# RPi_motor_driver.net
KiCad netlist of a schematic drawn in EAGLE
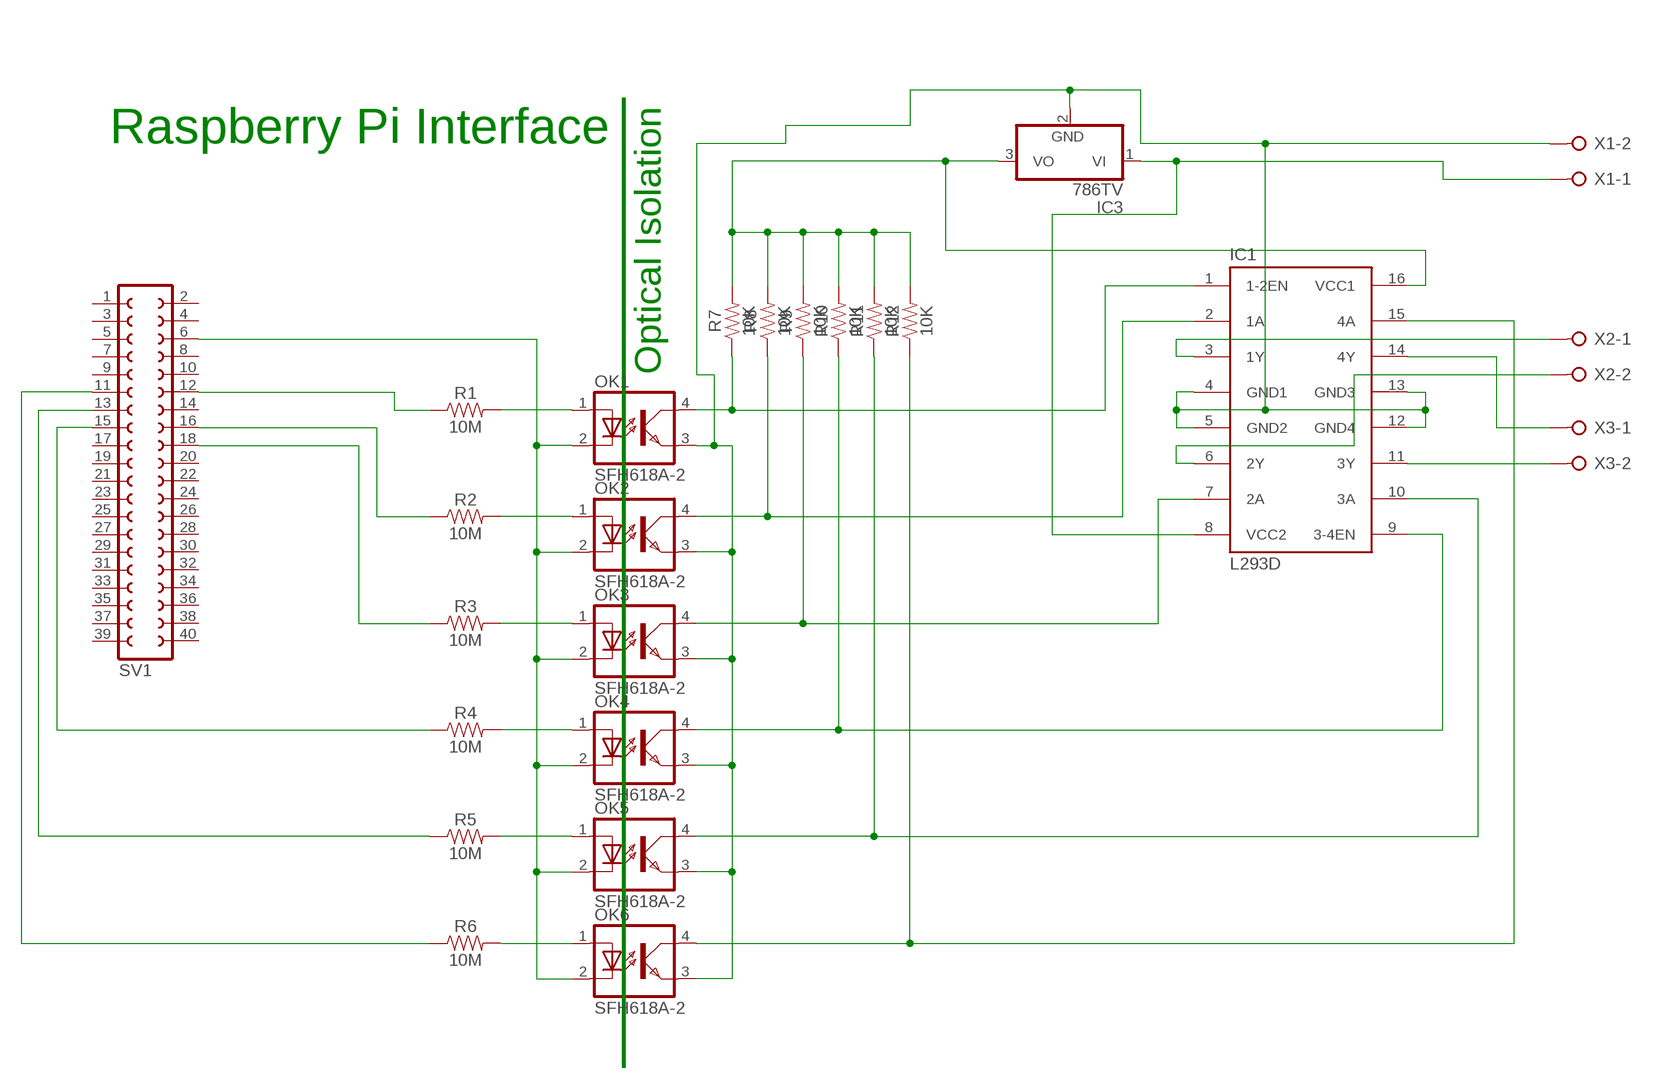
[diagram p0: schematic, sheet 1]

(export (version "E")
  (design (tool "Eeschema 10.0.6"))
  (components
    (comp (ref "IC1")
      (value "L293D")
      (footprint "eagle-import:DIL16")
      (libsource (lib "eagle-import") (part "L293D"))
    )
    (comp (ref "IC3")
      (value "786TV")
      (footprint "eagle-import:TO220V")
      (libsource (lib "eagle-import") (part "78TV6"))
    )
    (comp (ref "OK1")
      (value "SFH618A-2")
      (footprint "eagle-import:DIP4")
      (fields (field (name "MF") "VISHAY/TELEFUNKEN"))
      (libsource (lib "eagle-import") (part "SFH618?A-2"))
    )
    (comp (ref "OK2")
      (value "SFH618A-2")
      (footprint "eagle-import:DIP4")
      (fields (field (name "MF") "VISHAY/TELEFUNKEN"))
      (libsource (lib "eagle-import") (part "SFH618?A-2"))
    )
    (comp (ref "OK3")
      (value "SFH618A-2")
      (footprint "eagle-import:DIP4")
      (fields (field (name "MF") "VISHAY/TELEFUNKEN"))
      (libsource (lib "eagle-import") (part "SFH618?A-2"))
    )
    (comp (ref "OK4")
      (value "SFH618A-2")
      (footprint "eagle-import:DIP4")
      (fields (field (name "MF") "VISHAY/TELEFUNKEN"))
      (libsource (lib "eagle-import") (part "SFH618?A-2"))
    )
    (comp (ref "OK5")
      (value "SFH618A-2")
      (footprint "eagle-import:DIP4")
      (fields (field (name "MF") "VISHAY/TELEFUNKEN"))
      (libsource (lib "eagle-import") (part "SFH618?A-2"))
    )
    (comp (ref "OK6")
      (value "SFH618A-2")
      (footprint "eagle-import:DIP4")
      (fields (field (name "MF") "VISHAY/TELEFUNKEN"))
      (libsource (lib "eagle-import") (part "SFH618?A-2"))
    )
    (comp (ref "R1")
      (value "10M")
      (footprint "eagle-import:AXIAL-0.3")
      (libsource (lib "eagle-import") (part "10MOHM-HORIZ-1/4W-5%"))
    )
    (comp (ref "R2")
      (value "10M")
      (footprint "eagle-import:AXIAL-0.3")
      (libsource (lib "eagle-import") (part "10MOHM-HORIZ-1/4W-5%"))
    )
    (comp (ref "R3")
      (value "10M")
      (footprint "eagle-import:AXIAL-0.3")
      (libsource (lib "eagle-import") (part "10MOHM-HORIZ-1/4W-5%"))
    )
    (comp (ref "R4")
      (value "10M")
      (footprint "eagle-import:AXIAL-0.3")
      (libsource (lib "eagle-import") (part "10MOHM-HORIZ-1/4W-5%"))
    )
    (comp (ref "R5")
      (value "10M")
      (footprint "eagle-import:AXIAL-0.3")
      (libsource (lib "eagle-import") (part "10MOHM-HORIZ-1/4W-5%"))
    )
    (comp (ref "R6")
      (value "10M")
      (footprint "eagle-import:AXIAL-0.3")
      (libsource (lib "eagle-import") (part "10MOHM-HORIZ-1/4W-5%"))
    )
    (comp (ref "R7")
      (value "10K")
      (footprint "eagle-import:AXIAL-0.3")
      (libsource (lib "eagle-import") (part "10MOHM-HORIZ-1/4W-5%"))
    )
    (comp (ref "R8")
      (value "10K")
      (footprint "eagle-import:AXIAL-0.3")
      (libsource (lib "eagle-import") (part "10MOHM-HORIZ-1/4W-5%"))
    )
    (comp (ref "R9")
      (value "10K")
      (footprint "eagle-import:AXIAL-0.3")
      (libsource (lib "eagle-import") (part "10MOHM-HORIZ-1/4W-5%"))
    )
    (comp (ref "R10")
      (value "10K")
      (footprint "eagle-import:AXIAL-0.3")
      (libsource (lib "eagle-import") (part "10MOHM-HORIZ-1/4W-5%"))
    )
    (comp (ref "R11")
      (value "10K")
      (footprint "eagle-import:AXIAL-0.3")
      (libsource (lib "eagle-import") (part "10MOHM-HORIZ-1/4W-5%"))
    )
    (comp (ref "R12")
      (value "10K")
      (footprint "eagle-import:AXIAL-0.3")
      (libsource (lib "eagle-import") (part "10MOHM-HORIZ-1/4W-5%"))
    )
    (comp (ref "SV1")
      (value "FE20-2")
      (footprint "eagle-import:FE20-2")
      (libsource (lib "eagle-import") (part "FE20-2"))
    )
    (comp (ref "X1")
      (value "W237-02P")
      (footprint "eagle-import:W237-132")
      (libsource (lib "eagle-import") (part "W237-02P"))
    )
    (comp (ref "X2")
      (value "W237-02P")
      (footprint "eagle-import:W237-132")
      (libsource (lib "eagle-import") (part "W237-02P"))
    )
    (comp (ref "X3")
      (value "W237-02P")
      (footprint "eagle-import:W237-132")
      (libsource (lib "eagle-import") (part "W237-02P"))
    )
  )
  (nets
    (net (code "1") (name "Net-(IC1-1-2EN)") (class "Default")
      (node (ref "IC1") (pin "1") (pinfunction "1-2EN_1") (pintype "input"))
      (node (ref "OK1") (pin "4") (pinfunction "COL_4") (pintype "passive"))
      (node (ref "R7") (pin "P$1") (pinfunction "1_P$1") (pintype "passive"))
    )
    (net (code "2") (name "Net-(IC1-1A)") (class "Default")
      (node (ref "IC1") (pin "2") (pinfunction "1A_2") (pintype "input"))
      (node (ref "OK2") (pin "4") (pinfunction "COL_4") (pintype "passive"))
      (node (ref "R8") (pin "P$1") (pinfunction "1_P$1") (pintype "passive"))
    )
    (net (code "3") (name "Net-(IC1-1Y)") (class "Default")
      (node (ref "IC1") (pin "3") (pinfunction "1Y_3") (pintype "output"))
      (node (ref "X2") (pin "1") (pinfunction "KL_1") (pintype "passive"))
    )
    (net (code "4") (name "Net-(IC1-2A)") (class "Default")
      (node (ref "IC1") (pin "7") (pinfunction "2A_7") (pintype "input"))
      (node (ref "OK3") (pin "4") (pinfunction "COL_4") (pintype "passive"))
      (node (ref "R9") (pin "P$1") (pinfunction "1_P$1") (pintype "passive"))
    )
    (net (code "5") (name "Net-(IC1-2Y)") (class "Default")
      (node (ref "IC1") (pin "6") (pinfunction "2Y_6") (pintype "output"))
      (node (ref "X2") (pin "2") (pinfunction "KL_2") (pintype "passive"))
    )
    (net (code "6") (name "Net-(IC1-3-4EN)") (class "Default")
      (node (ref "IC1") (pin "9") (pinfunction "3-4EN_9") (pintype "input"))
      (node (ref "OK4") (pin "4") (pinfunction "COL_4") (pintype "passive"))
      (node (ref "R10") (pin "P$1") (pinfunction "1_P$1") (pintype "passive"))
    )
    (net (code "7") (name "Net-(IC1-3A)") (class "Default")
      (node (ref "IC1") (pin "10") (pinfunction "3A_10") (pintype "input"))
      (node (ref "OK5") (pin "4") (pinfunction "COL_4") (pintype "passive"))
      (node (ref "R11") (pin "P$1") (pinfunction "1_P$1") (pintype "passive"))
    )
    (net (code "8") (name "Net-(IC1-3Y)") (class "Default")
      (node (ref "IC1") (pin "11") (pinfunction "3Y_11") (pintype "output"))
      (node (ref "X3") (pin "2") (pinfunction "KL_2") (pintype "passive"))
    )
    (net (code "9") (name "Net-(IC1-4A)") (class "Default")
      (node (ref "IC1") (pin "15") (pinfunction "4A_15") (pintype "input"))
      (node (ref "OK6") (pin "4") (pinfunction "COL_4") (pintype "passive"))
      (node (ref "R12") (pin "P$1") (pinfunction "1_P$1") (pintype "passive"))
    )
    (net (code "10") (name "Net-(IC1-4Y)") (class "Default")
      (node (ref "IC1") (pin "14") (pinfunction "4Y_14") (pintype "output"))
      (node (ref "X3") (pin "1") (pinfunction "KL_1") (pintype "passive"))
    )
    (net (code "11") (name "Net-(IC1-GND1)") (class "Default")
      (node (ref "IC1") (pin "12") (pinfunction "GND4_12") (pintype "power_in"))
      (node (ref "IC1") (pin "13") (pinfunction "GND3_13") (pintype "power_in"))
      (node (ref "IC1") (pin "4") (pinfunction "GND1_4") (pintype "power_in"))
      (node (ref "IC1") (pin "5") (pinfunction "GND2_5") (pintype "power_in"))
      (node (ref "IC3") (pin "2") (pinfunction "GND_2") (pintype "passive"))
      (node (ref "OK1") (pin "3") (pinfunction "EMIT_3") (pintype "passive"))
      (node (ref "OK2") (pin "3") (pinfunction "EMIT_3") (pintype "passive"))
      (node (ref "OK3") (pin "3") (pinfunction "EMIT_3") (pintype "passive"))
      (node (ref "OK4") (pin "3") (pinfunction "EMIT_3") (pintype "passive"))
      (node (ref "OK5") (pin "3") (pinfunction "EMIT_3") (pintype "passive"))
      (node (ref "OK6") (pin "3") (pinfunction "EMIT_3") (pintype "passive"))
      (node (ref "X1") (pin "2") (pinfunction "KL_2") (pintype "passive"))
    )
    (net (code "12") (name "Net-(IC1-VCC1)") (class "Default")
      (node (ref "IC1") (pin "16") (pinfunction "VCC1_16") (pintype "power_in"))
      (node (ref "IC3") (pin "3") (pinfunction "VO_3") (pintype "passive"))
      (node (ref "R10") (pin "P$2") (pinfunction "2_P$2") (pintype "passive"))
      (node (ref "R11") (pin "P$2") (pinfunction "2_P$2") (pintype "passive"))
      (node (ref "R12") (pin "P$2") (pinfunction "2_P$2") (pintype "passive"))
      (node (ref "R7") (pin "P$2") (pinfunction "2_P$2") (pintype "passive"))
      (node (ref "R8") (pin "P$2") (pinfunction "2_P$2") (pintype "passive"))
      (node (ref "R9") (pin "P$2") (pinfunction "2_P$2") (pintype "passive"))
    )
    (net (code "13") (name "Net-(IC1-VCC2)") (class "Default")
      (node (ref "IC1") (pin "8") (pinfunction "VCC2_8") (pintype "power_in"))
      (node (ref "IC3") (pin "1") (pinfunction "VI_1") (pintype "input"))
      (node (ref "X1") (pin "1") (pinfunction "KL_1") (pintype "passive"))
    )
    (net (code "14") (name "Net-(OK1-A)") (class "Default")
      (node (ref "OK1") (pin "1") (pinfunction "A_1") (pintype "passive"))
      (node (ref "R1") (pin "P$2") (pinfunction "2_P$2") (pintype "passive"))
    )
    (net (code "15") (name "Net-(OK1-C)") (class "Default")
      (node (ref "OK1") (pin "2") (pinfunction "C_2") (pintype "passive"))
      (node (ref "OK2") (pin "2") (pinfunction "C_2") (pintype "passive"))
      (node (ref "OK3") (pin "2") (pinfunction "C_2") (pintype "passive"))
      (node (ref "OK4") (pin "2") (pinfunction "C_2") (pintype "passive"))
      (node (ref "OK5") (pin "2") (pinfunction "C_2") (pintype "passive"))
      (node (ref "OK6") (pin "2") (pinfunction "C_2") (pintype "passive"))
      (node (ref "SV1") (pin "6") (pinfunction "6_6") (pintype "passive"))
    )
    (net (code "16") (name "Net-(OK2-A)") (class "Default")
      (node (ref "OK2") (pin "1") (pinfunction "A_1") (pintype "passive"))
      (node (ref "R2") (pin "P$2") (pinfunction "2_P$2") (pintype "passive"))
    )
    (net (code "17") (name "Net-(OK3-A)") (class "Default")
      (node (ref "OK3") (pin "1") (pinfunction "A_1") (pintype "passive"))
      (node (ref "R3") (pin "P$2") (pinfunction "2_P$2") (pintype "passive"))
    )
    (net (code "18") (name "Net-(OK4-A)") (class "Default")
      (node (ref "OK4") (pin "1") (pinfunction "A_1") (pintype "passive"))
      (node (ref "R4") (pin "P$2") (pinfunction "2_P$2") (pintype "passive"))
    )
    (net (code "19") (name "Net-(OK5-A)") (class "Default")
      (node (ref "OK5") (pin "1") (pinfunction "A_1") (pintype "passive"))
      (node (ref "R5") (pin "P$2") (pinfunction "2_P$2") (pintype "passive"))
    )
    (net (code "20") (name "Net-(OK6-A)") (class "Default")
      (node (ref "OK6") (pin "1") (pinfunction "A_1") (pintype "passive"))
      (node (ref "R6") (pin "P$2") (pinfunction "2_P$2") (pintype "passive"))
    )
    (net (code "21") (name "Net-(R1-1)") (class "Default")
      (node (ref "R1") (pin "P$1") (pinfunction "1_P$1") (pintype "passive"))
      (node (ref "SV1") (pin "12") (pinfunction "12_12") (pintype "passive"))
    )
    (net (code "22") (name "Net-(R2-1)") (class "Default")
      (node (ref "R2") (pin "P$1") (pinfunction "1_P$1") (pintype "passive"))
      (node (ref "SV1") (pin "16") (pinfunction "16_16") (pintype "passive"))
    )
    (net (code "23") (name "Net-(R3-1)") (class "Default")
      (node (ref "R3") (pin "P$1") (pinfunction "1_P$1") (pintype "passive"))
      (node (ref "SV1") (pin "18") (pinfunction "18_18") (pintype "passive"))
    )
    (net (code "24") (name "Net-(R4-1)") (class "Default")
      (node (ref "R4") (pin "P$1") (pinfunction "1_P$1") (pintype "passive"))
      (node (ref "SV1") (pin "15") (pinfunction "15_15") (pintype "passive"))
    )
    (net (code "25") (name "Net-(R5-1)") (class "Default")
      (node (ref "R5") (pin "P$1") (pinfunction "1_P$1") (pintype "passive"))
      (node (ref "SV1") (pin "13") (pinfunction "13_13") (pintype "passive"))
    )
    (net (code "26") (name "Net-(R6-1)") (class "Default")
      (node (ref "R6") (pin "P$1") (pinfunction "1_P$1") (pintype "passive"))
      (node (ref "SV1") (pin "11") (pinfunction "11_11") (pintype "passive"))
    )
    (net (code "27") (name "unconnected-(SV1-Pad1)") (class "Default")
      (node (ref "SV1") (pin "1") (pinfunction "1_1") (pintype "passive"))
    )
    (net (code "28") (name "unconnected-(SV1-Pad2)") (class "Default")
      (node (ref "SV1") (pin "2") (pinfunction "2_2") (pintype "passive"))
    )
    (net (code "29") (name "unconnected-(SV1-Pad3)") (class "Default")
      (node (ref "SV1") (pin "3") (pinfunction "3_3") (pintype "passive"))
    )
    (net (code "30") (name "unconnected-(SV1-Pad4)") (class "Default")
      (node (ref "SV1") (pin "4") (pinfunction "4_4") (pintype "passive"))
    )
    (net (code "31") (name "unconnected-(SV1-Pad5)") (class "Default")
      (node (ref "SV1") (pin "5") (pinfunction "5_5") (pintype "passive"))
    )
    (net (code "32") (name "unconnected-(SV1-Pad7)") (class "Default")
      (node (ref "SV1") (pin "7") (pinfunction "7_7") (pintype "passive"))
    )
    (net (code "33") (name "unconnected-(SV1-Pad8)") (class "Default")
      (node (ref "SV1") (pin "8") (pinfunction "8_8") (pintype "passive"))
    )
    (net (code "34") (name "unconnected-(SV1-Pad9)") (class "Default")
      (node (ref "SV1") (pin "9") (pinfunction "9_9") (pintype "passive"))
    )
    (net (code "35") (name "unconnected-(SV1-Pad10)") (class "Default")
      (node (ref "SV1") (pin "10") (pinfunction "10_10") (pintype "passive"))
    )
    (net (code "36") (name "unconnected-(SV1-Pad14)") (class "Default")
      (node (ref "SV1") (pin "14") (pinfunction "14_14") (pintype "passive"))
    )
    (net (code "37") (name "unconnected-(SV1-Pad17)") (class "Default")
      (node (ref "SV1") (pin "17") (pinfunction "17_17") (pintype "passive"))
    )
    (net (code "38") (name "unconnected-(SV1-Pad19)") (class "Default")
      (node (ref "SV1") (pin "19") (pinfunction "19_19") (pintype "passive"))
    )
    (net (code "39") (name "unconnected-(SV1-Pad20)") (class "Default")
      (node (ref "SV1") (pin "20") (pinfunction "20_20") (pintype "passive"))
    )
    (net (code "40") (name "unconnected-(SV1-Pad21)") (class "Default")
      (node (ref "SV1") (pin "21") (pinfunction "21_21") (pintype "passive"))
    )
    (net (code "41") (name "unconnected-(SV1-Pad22)") (class "Default")
      (node (ref "SV1") (pin "22") (pinfunction "22_22") (pintype "passive"))
    )
    (net (code "42") (name "unconnected-(SV1-Pad23)") (class "Default")
      (node (ref "SV1") (pin "23") (pinfunction "23_23") (pintype "passive"))
    )
    (net (code "43") (name "unconnected-(SV1-Pad24)") (class "Default")
      (node (ref "SV1") (pin "24") (pinfunction "24_24") (pintype "passive"))
    )
    (net (code "44") (name "unconnected-(SV1-Pad25)") (class "Default")
      (node (ref "SV1") (pin "25") (pinfunction "25_25") (pintype "passive"))
    )
    (net (code "45") (name "unconnected-(SV1-Pad26)") (class "Default")
      (node (ref "SV1") (pin "26") (pinfunction "26_26") (pintype "passive"))
    )
    (net (code "46") (name "unconnected-(SV1-Pad27)") (class "Default")
      (node (ref "SV1") (pin "27") (pinfunction "27_27") (pintype "passive"))
    )
    (net (code "47") (name "unconnected-(SV1-Pad28)") (class "Default")
      (node (ref "SV1") (pin "28") (pinfunction "28_28") (pintype "passive"))
    )
    (net (code "48") (name "unconnected-(SV1-Pad29)") (class "Default")
      (node (ref "SV1") (pin "29") (pinfunction "29_29") (pintype "passive"))
    )
    (net (code "49") (name "unconnected-(SV1-Pad30)") (class "Default")
      (node (ref "SV1") (pin "30") (pinfunction "30_30") (pintype "passive"))
    )
    (net (code "50") (name "unconnected-(SV1-Pad31)") (class "Default")
      (node (ref "SV1") (pin "31") (pinfunction "31_31") (pintype "passive"))
    )
    (net (code "51") (name "unconnected-(SV1-Pad32)") (class "Default")
      (node (ref "SV1") (pin "32") (pinfunction "32_32") (pintype "passive"))
    )
    (net (code "52") (name "unconnected-(SV1-Pad33)") (class "Default")
      (node (ref "SV1") (pin "33") (pinfunction "33_33") (pintype "passive"))
    )
    (net (code "53") (name "unconnected-(SV1-Pad34)") (class "Default")
      (node (ref "SV1") (pin "34") (pinfunction "34_34") (pintype "passive"))
    )
    (net (code "54") (name "unconnected-(SV1-Pad35)") (class "Default")
      (node (ref "SV1") (pin "35") (pinfunction "35_35") (pintype "passive"))
    )
    (net (code "55") (name "unconnected-(SV1-Pad36)") (class "Default")
      (node (ref "SV1") (pin "36") (pinfunction "36_36") (pintype "passive"))
    )
    (net (code "56") (name "unconnected-(SV1-Pad37)") (class "Default")
      (node (ref "SV1") (pin "37") (pinfunction "37_37") (pintype "passive"))
    )
    (net (code "57") (name "unconnected-(SV1-Pad38)") (class "Default")
      (node (ref "SV1") (pin "38") (pinfunction "38_38") (pintype "passive"))
    )
    (net (code "58") (name "unconnected-(SV1-Pad39)") (class "Default")
      (node (ref "SV1") (pin "39") (pinfunction "39_39") (pintype "passive"))
    )
    (net (code "59") (name "unconnected-(SV1-Pad40)") (class "Default")
      (node (ref "SV1") (pin "40") (pinfunction "40_40") (pintype "passive"))
    )
  )
)
